# Arduino_Diff_COMM.net
KiCad netlist of a schematic drawn in EAGLE
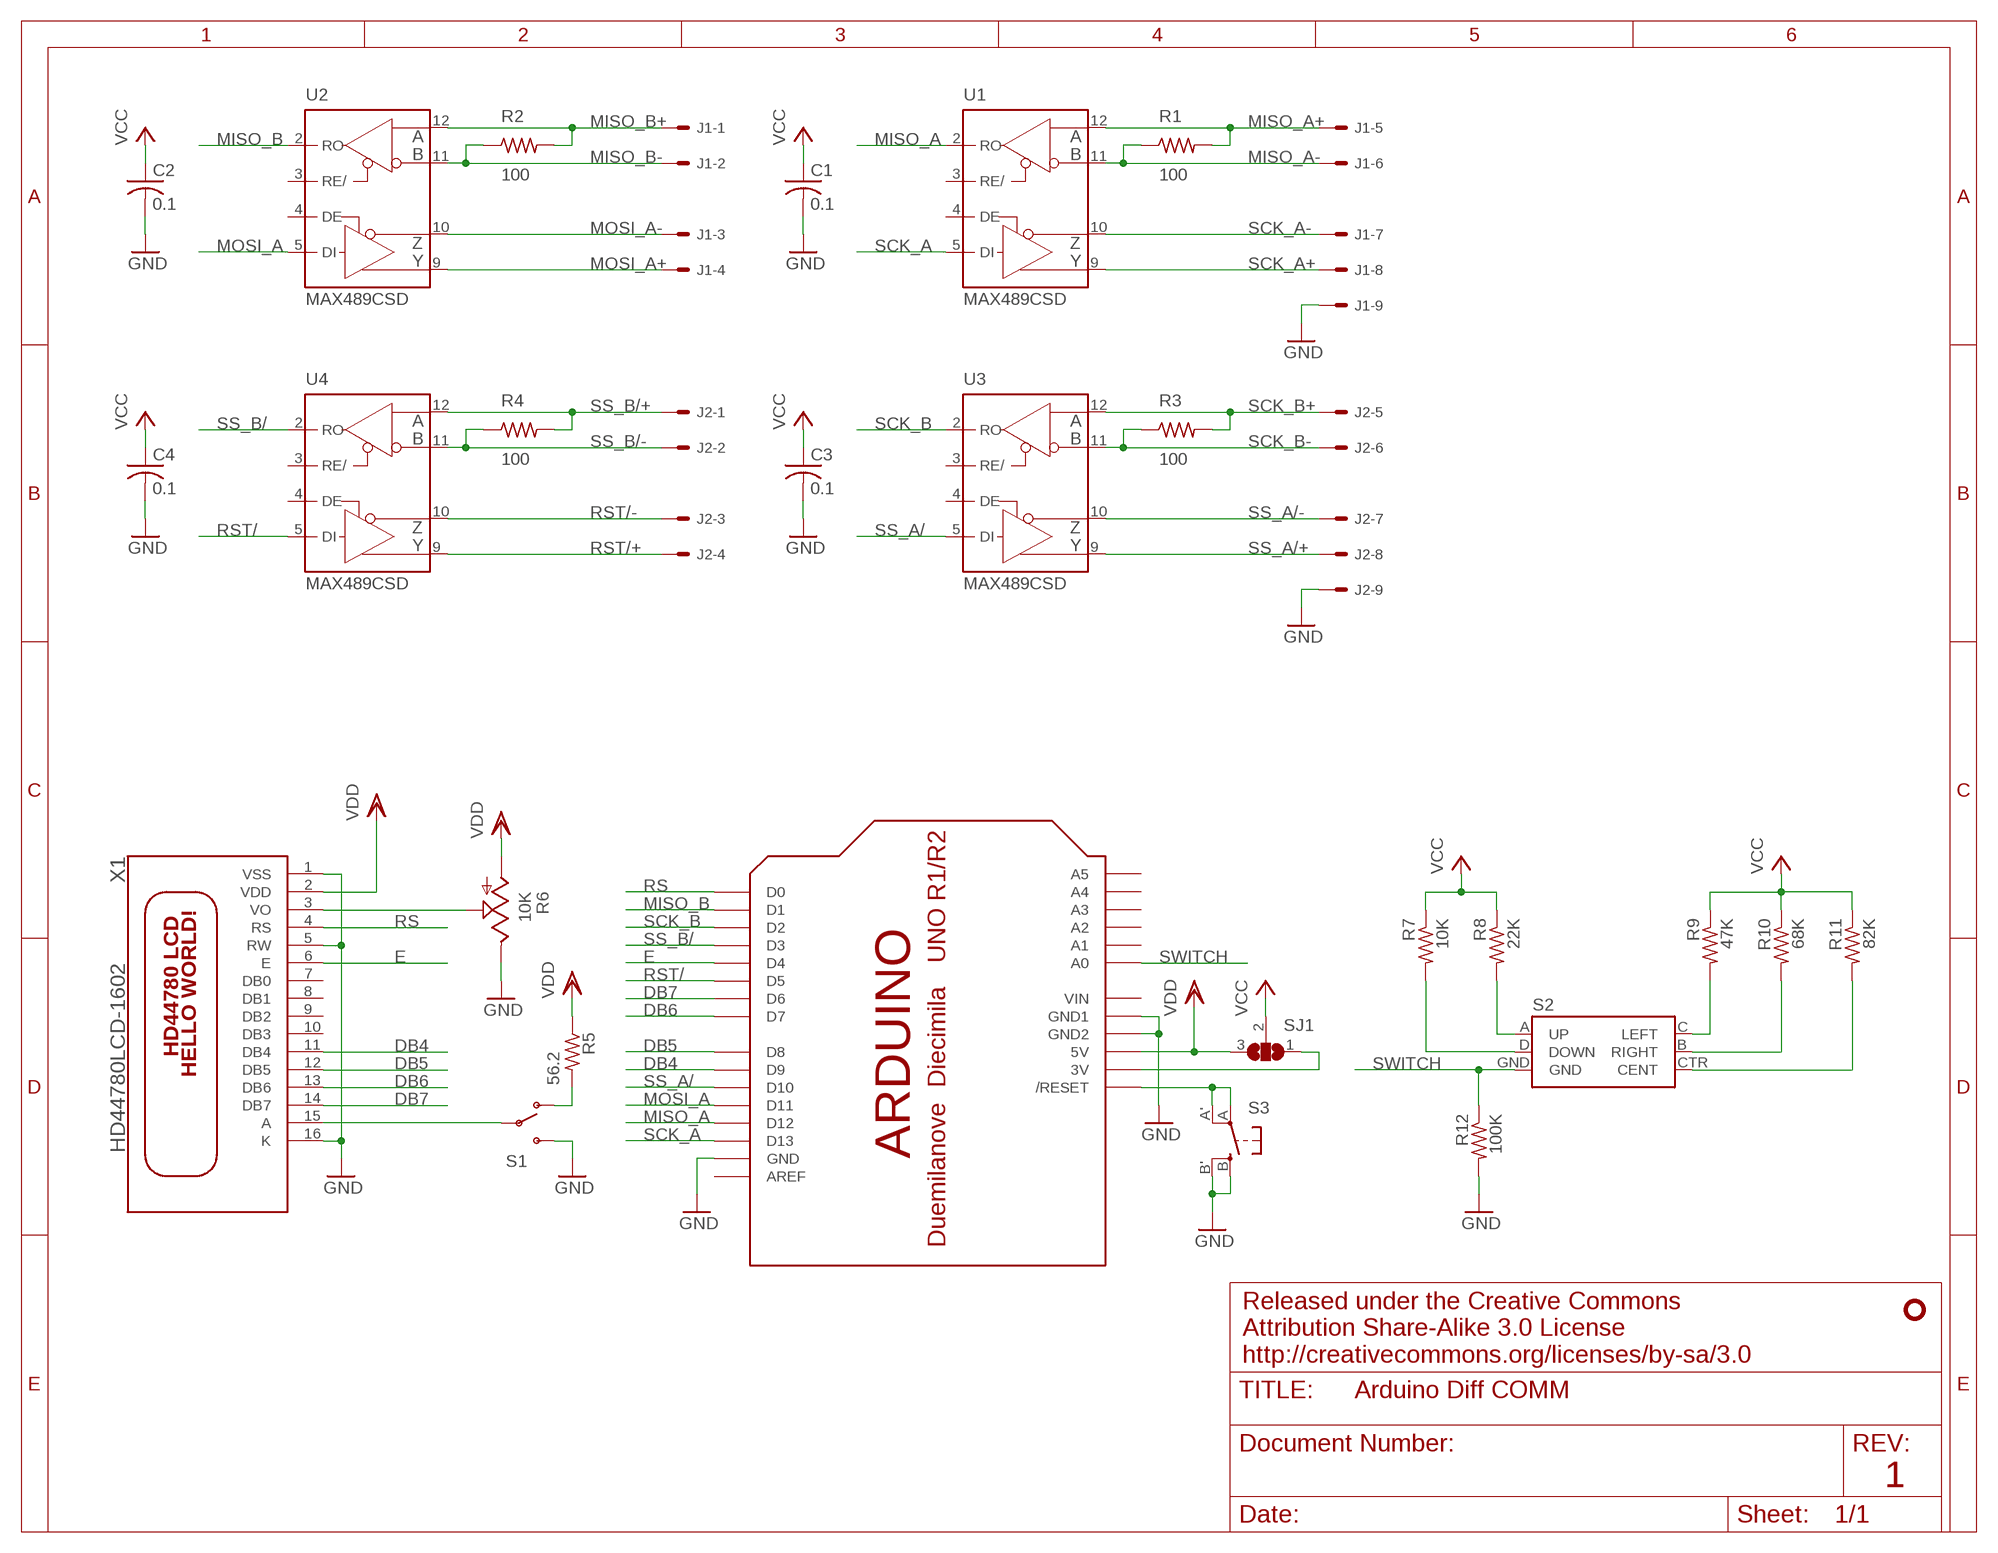
[diagram p0: schematic, sheet 1]

(export (version "E")
  (design (tool "Eeschema 10.0.6"))
  (components
    (comp (ref "C1")
      (value "0.1")
      (footprint "eagle-import:C0603K")
      (libsource (lib "eagle-import") (part "C-USC0603K"))
    )
    (comp (ref "C2")
      (value "0.1")
      (footprint "eagle-import:C0603K")
      (libsource (lib "eagle-import") (part "C-USC0603K"))
    )
    (comp (ref "C3")
      (value "0.1")
      (footprint "eagle-import:C0603K")
      (libsource (lib "eagle-import") (part "C-USC0603K"))
    )
    (comp (ref "C4")
      (value "0.1")
      (footprint "eagle-import:C0603K")
      (libsource (lib "eagle-import") (part "C-USC0603K"))
    )
    (comp (ref "J1")
      (value "22-05-7098-09")
      (footprint "eagle-import:7395-09")
      (libsource (lib "eagle-import") (part "22-?-0905-7098"))
    )
    (comp (ref "J2")
      (value "22-05-7098-09")
      (footprint "eagle-import:7395-09")
      (libsource (lib "eagle-import") (part "22-?-0905-7098"))
    )
    (comp (ref "R1")
      (value "100")
      (footprint "eagle-import:R1206")
      (libsource (lib "eagle-import") (part "R-US_R1206"))
    )
    (comp (ref "R2")
      (value "100")
      (footprint "eagle-import:R1206")
      (libsource (lib "eagle-import") (part "R-US_R1206"))
    )
    (comp (ref "R3")
      (value "100")
      (footprint "eagle-import:R1206")
      (libsource (lib "eagle-import") (part "R-US_R1206"))
    )
    (comp (ref "R4")
      (value "100")
      (footprint "eagle-import:R1206")
      (libsource (lib "eagle-import") (part "R-US_R1206"))
    )
    (comp (ref "R5")
      (value "56.2")
      (footprint "eagle-import:R0805")
      (libsource (lib "eagle-import") (part "R-US_R0805"))
    )
    (comp (ref "R6")
      (value "10K")
      (footprint "eagle-import:3223G")
      (libsource (lib "eagle-import") (part "TRIM_US-3223G"))
    )
    (comp (ref "R7")
      (value "10K")
      (footprint "eagle-import:R0805")
      (libsource (lib "eagle-import") (part "R-US_R0805"))
    )
    (comp (ref "R8")
      (value "22K")
      (footprint "eagle-import:R0805")
      (libsource (lib "eagle-import") (part "R-US_R0805"))
    )
    (comp (ref "R9")
      (value "47K")
      (footprint "eagle-import:R0805")
      (libsource (lib "eagle-import") (part "R-US_R0805"))
    )
    (comp (ref "R10")
      (value "68K")
      (footprint "eagle-import:R0805")
      (libsource (lib "eagle-import") (part "R-US_R0805"))
    )
    (comp (ref "R11")
      (value "82K")
      (footprint "eagle-import:R0805")
      (libsource (lib "eagle-import") (part "R-US_R0805"))
    )
    (comp (ref "R12")
      (value "100K")
      (footprint "eagle-import:R0805")
      (libsource (lib "eagle-import") (part "R-US_R0805"))
    )
    (comp (ref "S1")
      (value "SWITCH_SPDT")
      (footprint "eagle-import:KPS-1290")
      (libsource (lib "eagle-import") (part "SWITCH_SPDT"))
    )
    (comp (ref "S2")
      (value "JOYSTICK_MINI")
      (footprint "eagle-import:JOYSTICK_MINI")
      (libsource (lib "eagle-import") (part "JOYSTICK_MINI"))
    )
    (comp (ref "S3")
      (value "SPST_TACT-EVQQ2")
      (footprint "eagle-import:EVQ-Q2")
      (libsource (lib "eagle-import") (part "SPST_TACT-EVQQ2"))
    )
    (comp (ref "SJ1")
      (value "SJ2W")
      (footprint "eagle-import:SJ_2")
      (libsource (lib "eagle-import") (part "SJ2W"))
    )
    (comp (ref "U$1")
      (value "ARDUINO-NOHOLE")
      (footprint "eagle-import:ARDUINO-NOHOLE")
      (libsource (lib "eagle-import") (part "ARDUINO-NOHOLE"))
    )
    (comp (ref "U$2")
      (value "PENGUIN_LOGOCOPPER")
      (footprint "eagle-import:PENGUIN_COPPER")
      (libsource (lib "eagle-import") (part "PENGUIN_LOGOCOPPER"))
    )
    (comp (ref "U1")
      (value "MAX489CSD")
      (footprint "eagle-import:SO14")
      (fields (field (name "MF") "MAXIM"))
      (libsource (lib "eagle-import") (part "MAX489CSD"))
    )
    (comp (ref "U2")
      (value "MAX489CSD")
      (footprint "eagle-import:SO14")
      (fields (field (name "MF") "MAXIM"))
      (libsource (lib "eagle-import") (part "MAX489CSD"))
    )
    (comp (ref "U3")
      (value "MAX489CSD")
      (footprint "eagle-import:SO14")
      (fields (field (name "MF") "MAXIM"))
      (libsource (lib "eagle-import") (part "MAX489CSD"))
    )
    (comp (ref "U4")
      (value "MAX489CSD")
      (footprint "eagle-import:SO14")
      (fields (field (name "MF") "MAXIM"))
      (libsource (lib "eagle-import") (part "MAX489CSD"))
    )
    (comp (ref "X1")
      (value "HD44780LCD-1602")
      (footprint "eagle-import:LCD1602")
      (libsource (lib "eagle-import") (part "HD44780LCD-1602"))
    )
  )
  (nets
    (net (code "1") (name "/DB4") (class "Default")
      (node (ref "U$1") (pin "D9") (pinfunction "D9_D9") (pintype "bidirectional"))
      (node (ref "X1") (pin "11") (pinfunction "DB4_11") (pintype "bidirectional"))
    )
    (net (code "2") (name "/DB5") (class "Default")
      (node (ref "U$1") (pin "D8") (pinfunction "D8_D8") (pintype "bidirectional"))
      (node (ref "X1") (pin "12") (pinfunction "DB5_12") (pintype "bidirectional"))
    )
    (net (code "3") (name "/DB6") (class "Default")
      (node (ref "U$1") (pin "D7") (pinfunction "D7_D7") (pintype "bidirectional"))
      (node (ref "X1") (pin "13") (pinfunction "DB6_13") (pintype "bidirectional"))
    )
    (net (code "4") (name "/DB7") (class "Default")
      (node (ref "U$1") (pin "D6") (pinfunction "D6_D6") (pintype "bidirectional"))
      (node (ref "X1") (pin "14") (pinfunction "DB7_14") (pintype "bidirectional"))
    )
    (net (code "5") (name "/E") (class "Default")
      (node (ref "U$1") (pin "D4") (pinfunction "D4_D4") (pintype "bidirectional"))
      (node (ref "X1") (pin "6") (pinfunction "E_6") (pintype "input"))
    )
    (net (code "6") (name "/MISO_A") (class "Default")
      (node (ref "U$1") (pin "D12") (pinfunction "D12_D12") (pintype "bidirectional"))
      (node (ref "U1") (pin "2") (pinfunction "RO_2") (pintype "output"))
    )
    (net (code "7") (name "/MISO_A+") (class "Default")
      (node (ref "J1") (pin "5") (pinfunction "S_5") (pintype "passive"))
      (node (ref "R1") (pin "2") (pinfunction "2_2") (pintype "passive"))
      (node (ref "U1") (pin "12") (pinfunction "A_12") (pintype "passive"))
    )
    (net (code "8") (name "/MISO_A-") (class "Default")
      (node (ref "J1") (pin "6") (pinfunction "S_6") (pintype "passive"))
      (node (ref "R1") (pin "1") (pinfunction "1_1") (pintype "passive"))
      (node (ref "U1") (pin "11") (pinfunction "B_11") (pintype "passive"))
    )
    (net (code "9") (name "/MISO_B") (class "Default")
      (node (ref "U$1") (pin "D1") (pinfunction "D1_D1") (pintype "bidirectional"))
      (node (ref "U2") (pin "2") (pinfunction "RO_2") (pintype "output"))
    )
    (net (code "10") (name "/MISO_B+") (class "Default")
      (node (ref "J1") (pin "1") (pinfunction "S_1") (pintype "passive"))
      (node (ref "R2") (pin "2") (pinfunction "2_2") (pintype "passive"))
      (node (ref "U2") (pin "12") (pinfunction "A_12") (pintype "passive"))
    )
    (net (code "11") (name "/MISO_B-") (class "Default")
      (node (ref "J1") (pin "2") (pinfunction "S_2") (pintype "passive"))
      (node (ref "R2") (pin "1") (pinfunction "1_1") (pintype "passive"))
      (node (ref "U2") (pin "11") (pinfunction "B_11") (pintype "passive"))
    )
    (net (code "12") (name "/MOSI_A") (class "Default")
      (node (ref "U$1") (pin "D11") (pinfunction "D11_D11") (pintype "bidirectional"))
      (node (ref "U2") (pin "5") (pinfunction "DI_5") (pintype "input"))
    )
    (net (code "13") (name "/MOSI_A+") (class "Default")
      (node (ref "J1") (pin "4") (pinfunction "S_4") (pintype "passive"))
      (node (ref "U2") (pin "9") (pinfunction "Y_9") (pintype "passive"))
    )
    (net (code "14") (name "/MOSI_A-") (class "Default")
      (node (ref "J1") (pin "3") (pinfunction "S_3") (pintype "passive"))
      (node (ref "U2") (pin "10") (pinfunction "Z_10") (pintype "passive"))
    )
    (net (code "15") (name "/RS") (class "Default")
      (node (ref "U$1") (pin "D0") (pinfunction "D0_D0") (pintype "bidirectional"))
      (node (ref "X1") (pin "4") (pinfunction "RS_4") (pintype "input"))
    )
    (net (code "16") (name "/RST{slash}") (class "Default")
      (node (ref "U$1") (pin "D5") (pinfunction "D5_D5") (pintype "bidirectional"))
      (node (ref "U4") (pin "5") (pinfunction "DI_5") (pintype "input"))
    )
    (net (code "17") (name "/RST{slash}+") (class "Default")
      (node (ref "J2") (pin "4") (pinfunction "S_4") (pintype "passive"))
      (node (ref "U4") (pin "9") (pinfunction "Y_9") (pintype "passive"))
    )
    (net (code "18") (name "/RST{slash}-") (class "Default")
      (node (ref "J2") (pin "3") (pinfunction "S_3") (pintype "passive"))
      (node (ref "U4") (pin "10") (pinfunction "Z_10") (pintype "passive"))
    )
    (net (code "19") (name "/SCK_A") (class "Default")
      (node (ref "U$1") (pin "D13") (pinfunction "D13_D13") (pintype "bidirectional"))
      (node (ref "U1") (pin "5") (pinfunction "DI_5") (pintype "input"))
    )
    (net (code "20") (name "/SCK_A+") (class "Default")
      (node (ref "J1") (pin "8") (pinfunction "S_8") (pintype "passive"))
      (node (ref "U1") (pin "9") (pinfunction "Y_9") (pintype "passive"))
    )
    (net (code "21") (name "/SCK_A-") (class "Default")
      (node (ref "J1") (pin "7") (pinfunction "S_7") (pintype "passive"))
      (node (ref "U1") (pin "10") (pinfunction "Z_10") (pintype "passive"))
    )
    (net (code "22") (name "/SCK_B") (class "Default")
      (node (ref "U$1") (pin "D2") (pinfunction "D2_D2") (pintype "bidirectional"))
      (node (ref "U3") (pin "2") (pinfunction "RO_2") (pintype "output"))
    )
    (net (code "23") (name "/SCK_B+") (class "Default")
      (node (ref "J2") (pin "5") (pinfunction "S_5") (pintype "passive"))
      (node (ref "R3") (pin "2") (pinfunction "2_2") (pintype "passive"))
      (node (ref "U3") (pin "12") (pinfunction "A_12") (pintype "passive"))
    )
    (net (code "24") (name "/SCK_B-") (class "Default")
      (node (ref "J2") (pin "6") (pinfunction "S_6") (pintype "passive"))
      (node (ref "R3") (pin "1") (pinfunction "1_1") (pintype "passive"))
      (node (ref "U3") (pin "11") (pinfunction "B_11") (pintype "passive"))
    )
    (net (code "25") (name "/SS_A{slash}") (class "Default")
      (node (ref "U$1") (pin "D10") (pinfunction "D10_D10") (pintype "bidirectional"))
      (node (ref "U3") (pin "5") (pinfunction "DI_5") (pintype "input"))
    )
    (net (code "26") (name "/SS_A{slash}+") (class "Default")
      (node (ref "J2") (pin "8") (pinfunction "S_8") (pintype "passive"))
      (node (ref "U3") (pin "9") (pinfunction "Y_9") (pintype "passive"))
    )
    (net (code "27") (name "/SS_A{slash}-") (class "Default")
      (node (ref "J2") (pin "7") (pinfunction "S_7") (pintype "passive"))
      (node (ref "U3") (pin "10") (pinfunction "Z_10") (pintype "passive"))
    )
    (net (code "28") (name "/SS_B{slash}") (class "Default")
      (node (ref "U$1") (pin "D3") (pinfunction "D3_D3") (pintype "bidirectional"))
      (node (ref "U4") (pin "2") (pinfunction "RO_2") (pintype "output"))
    )
    (net (code "29") (name "/SS_B{slash}+") (class "Default")
      (node (ref "J2") (pin "1") (pinfunction "S_1") (pintype "passive"))
      (node (ref "R4") (pin "2") (pinfunction "2_2") (pintype "passive"))
      (node (ref "U4") (pin "12") (pinfunction "A_12") (pintype "passive"))
    )
    (net (code "30") (name "/SS_B{slash}-") (class "Default")
      (node (ref "J2") (pin "2") (pinfunction "S_2") (pintype "passive"))
      (node (ref "R4") (pin "1") (pinfunction "1_1") (pintype "passive"))
      (node (ref "U4") (pin "11") (pinfunction "B_11") (pintype "passive"))
    )
    (net (code "31") (name "/SWITCH") (class "Default")
      (node (ref "R12") (pin "1") (pinfunction "1_1") (pintype "passive"))
      (node (ref "S2") (pin "GND") (pinfunction "GND_GND") (pintype "bidirectional"))
      (node (ref "U$1") (pin "A0") (pinfunction "A0_A0") (pintype "bidirectional"))
    )
    (net (code "32") (name "/VIN") (class "Default")
      (node (ref "U$1") (pin "VIN") (pinfunction "VIN_VIN") (pintype "power_in"))
    )
    (net (code "33") (name "GND") (class "Default")
      (node (ref "C1") (pin "2") (pinfunction "2_2") (pintype "passive"))
      (node (ref "C2") (pin "2") (pinfunction "2_2") (pintype "passive"))
      (node (ref "C3") (pin "2") (pinfunction "2_2") (pintype "passive"))
      (node (ref "C4") (pin "2") (pinfunction "2_2") (pintype "passive"))
      (node (ref "J1") (pin "9") (pinfunction "S_9") (pintype "passive"))
      (node (ref "J2") (pin "9") (pinfunction "S_9") (pintype "passive"))
      (node (ref "R12") (pin "2") (pinfunction "2_2") (pintype "passive"))
      (node (ref "R6") (pin "3") (pinfunction "E_3") (pintype "passive"))
      (node (ref "S1") (pin "S") (pinfunction "S_S") (pintype "passive"))
      (node (ref "S3") (pin "B") (pinfunction "S_B") (pintype "passive"))
      (node (ref "S3") (pin "B'") (pinfunction "S1_B'") (pintype "passive"))
      (node (ref "U$1") (pin "GND") (pinfunction "GND_GND") (pintype "power_in"))
      (node (ref "U$1") (pin "GND1") (pinfunction "GND1_GND1") (pintype "power_in"))
      (node (ref "U$1") (pin "GND2") (pinfunction "GND2_GND2") (pintype "power_in"))
      (node (ref "X1") (pin "1") (pinfunction "VSS_1") (pintype "power_in"))
      (node (ref "X1") (pin "16") (pinfunction "K_16") (pintype "input"))
      (node (ref "X1") (pin "5") (pinfunction "RW_5") (pintype "input"))
    )
    (net (code "34") (name "Net-(R5-Pad2)") (class "Default")
      (node (ref "R5") (pin "2") (pinfunction "2_2") (pintype "passive"))
      (node (ref "S1") (pin "O") (pinfunction "O_O") (pintype "passive"))
    )
    (net (code "35") (name "Net-(R6-S)") (class "Default")
      (node (ref "R6") (pin "2") (pinfunction "S_2") (pintype "passive"))
      (node (ref "X1") (pin "3") (pinfunction "VO_3") (pintype "input"))
    )
    (net (code "36") (name "Net-(S2-CENT)") (class "Default")
      (node (ref "R11") (pin "2") (pinfunction "2_2") (pintype "passive"))
      (node (ref "S2") (pin "CTR") (pinfunction "CENT_CTR") (pintype "bidirectional"))
    )
    (net (code "37") (name "Net-(S2-DOWN)") (class "Default")
      (node (ref "R7") (pin "2") (pinfunction "2_2") (pintype "passive"))
      (node (ref "S2") (pin "D") (pinfunction "DOWN_D") (pintype "bidirectional"))
    )
    (net (code "38") (name "Net-(S2-LEFT)") (class "Default")
      (node (ref "R9") (pin "2") (pinfunction "2_2") (pintype "passive"))
      (node (ref "S2") (pin "C") (pinfunction "LEFT_C") (pintype "bidirectional"))
    )
    (net (code "39") (name "Net-(S2-RIGHT)") (class "Default")
      (node (ref "R10") (pin "2") (pinfunction "2_2") (pintype "passive"))
      (node (ref "S2") (pin "B") (pinfunction "RIGHT_B") (pintype "bidirectional"))
    )
    (net (code "40") (name "Net-(S2-UP)") (class "Default")
      (node (ref "R8") (pin "2") (pinfunction "2_2") (pintype "passive"))
      (node (ref "S2") (pin "A") (pinfunction "UP_A") (pintype "bidirectional"))
    )
    (net (code "41") (name "Net-(S3-P)") (class "Default")
      (node (ref "S3") (pin "A") (pinfunction "P_A") (pintype "passive"))
      (node (ref "S3") (pin "A'") (pinfunction "P1_A'") (pintype "passive"))
      (node (ref "U$1") (pin "RESET") (pinfunction "/RESET_RESET") (pintype "bidirectional"))
    )
    (net (code "42") (name "Net-(SJ1-Pad1)") (class "Default")
      (node (ref "SJ1") (pin "1") (pinfunction "1_1") (pintype "passive"))
      (node (ref "U$1") (pin "3V") (pinfunction "3V_3V") (pintype "power_in"))
    )
    (net (code "43") (name "Net-(X1-A)") (class "Default")
      (node (ref "S1") (pin "P") (pinfunction "P_P") (pintype "passive"))
      (node (ref "X1") (pin "15") (pinfunction "A_15") (pintype "input"))
    )
    (net (code "44") (name "VCC") (class "Default")
      (node (ref "C1") (pin "1") (pinfunction "1_1") (pintype "passive"))
      (node (ref "C2") (pin "1") (pinfunction "1_1") (pintype "passive"))
      (node (ref "C3") (pin "1") (pinfunction "1_1") (pintype "passive"))
      (node (ref "C4") (pin "1") (pinfunction "1_1") (pintype "passive"))
      (node (ref "R10") (pin "1") (pinfunction "1_1") (pintype "passive"))
      (node (ref "R11") (pin "1") (pinfunction "1_1") (pintype "passive"))
      (node (ref "R7") (pin "1") (pinfunction "1_1") (pintype "passive"))
      (node (ref "R8") (pin "1") (pinfunction "1_1") (pintype "passive"))
      (node (ref "R9") (pin "1") (pinfunction "1_1") (pintype "passive"))
      (node (ref "SJ1") (pin "2") (pinfunction "2_2") (pintype "passive"))
    )
    (net (code "45") (name "VDD") (class "Default")
      (node (ref "R5") (pin "1") (pinfunction "1_1") (pintype "passive"))
      (node (ref "R6") (pin "1") (pinfunction "A_1") (pintype "passive"))
      (node (ref "SJ1") (pin "3") (pinfunction "3_3") (pintype "passive"))
      (node (ref "U$1") (pin "5V") (pinfunction "5V_5V") (pintype "power_in"))
      (node (ref "X1") (pin "2") (pinfunction "VDD_2") (pintype "power_in"))
    )
    (net (code "46") (name "unconnected-(U$1-PadA1)") (class "Default")
      (node (ref "U$1") (pin "A1") (pinfunction "A1_A1") (pintype "bidirectional"))
    )
    (net (code "47") (name "unconnected-(U$1-PadA2)") (class "Default")
      (node (ref "U$1") (pin "A2") (pinfunction "A2_A2") (pintype "bidirectional"))
    )
    (net (code "48") (name "unconnected-(U$1-PadA3)") (class "Default")
      (node (ref "U$1") (pin "A3") (pinfunction "A3_A3") (pintype "bidirectional"))
    )
    (net (code "49") (name "unconnected-(U$1-PadA4)") (class "Default")
      (node (ref "U$1") (pin "A4") (pinfunction "A4_A4") (pintype "bidirectional"))
    )
    (net (code "50") (name "unconnected-(U$1-PadA5)") (class "Default")
      (node (ref "U$1") (pin "A5") (pinfunction "A5_A5") (pintype "bidirectional"))
    )
    (net (code "51") (name "unconnected-(U$1-PadAREF)") (class "Default")
      (node (ref "U$1") (pin "AREF") (pinfunction "AREF_AREF") (pintype "bidirectional"))
    )
    (net (code "52") (name "unconnected-(U1D-DE-Pad4)") (class "Default")
      (node (ref "U1") (pin "4") (pinfunction "DE_4") (pintype "input"))
    )
    (net (code "53") (name "unconnected-(U1D-RE{slash}-Pad3)") (class "Default")
      (node (ref "U1") (pin "3") (pinfunction "RE/_3") (pintype "input"))
    )
    (net (code "54") (name "unconnected-(U2D-DE-Pad4)") (class "Default")
      (node (ref "U2") (pin "4") (pinfunction "DE_4") (pintype "input"))
    )
    (net (code "55") (name "unconnected-(U2D-RE{slash}-Pad3)") (class "Default")
      (node (ref "U2") (pin "3") (pinfunction "RE/_3") (pintype "input"))
    )
    (net (code "56") (name "unconnected-(U3D-DE-Pad4)") (class "Default")
      (node (ref "U3") (pin "4") (pinfunction "DE_4") (pintype "input"))
    )
    (net (code "57") (name "unconnected-(U3D-RE{slash}-Pad3)") (class "Default")
      (node (ref "U3") (pin "3") (pinfunction "RE/_3") (pintype "input"))
    )
    (net (code "58") (name "unconnected-(U4D-DE-Pad4)") (class "Default")
      (node (ref "U4") (pin "4") (pinfunction "DE_4") (pintype "input"))
    )
    (net (code "59") (name "unconnected-(U4D-RE{slash}-Pad3)") (class "Default")
      (node (ref "U4") (pin "3") (pinfunction "RE/_3") (pintype "input"))
    )
    (net (code "60") (name "unconnected-(X1-DB0-Pad7)") (class "Default")
      (node (ref "X1") (pin "7") (pinfunction "DB0_7") (pintype "bidirectional"))
    )
    (net (code "61") (name "unconnected-(X1-DB1-Pad8)") (class "Default")
      (node (ref "X1") (pin "8") (pinfunction "DB1_8") (pintype "bidirectional"))
    )
    (net (code "62") (name "unconnected-(X1-DB2-Pad9)") (class "Default")
      (node (ref "X1") (pin "9") (pinfunction "DB2_9") (pintype "bidirectional"))
    )
    (net (code "63") (name "unconnected-(X1-DB3-Pad10)") (class "Default")
      (node (ref "X1") (pin "10") (pinfunction "DB3_10") (pintype "bidirectional"))
    )
  )
)
